# 2025-03-23.net
KiCad netlist of a schematic drawn in EasyEDA
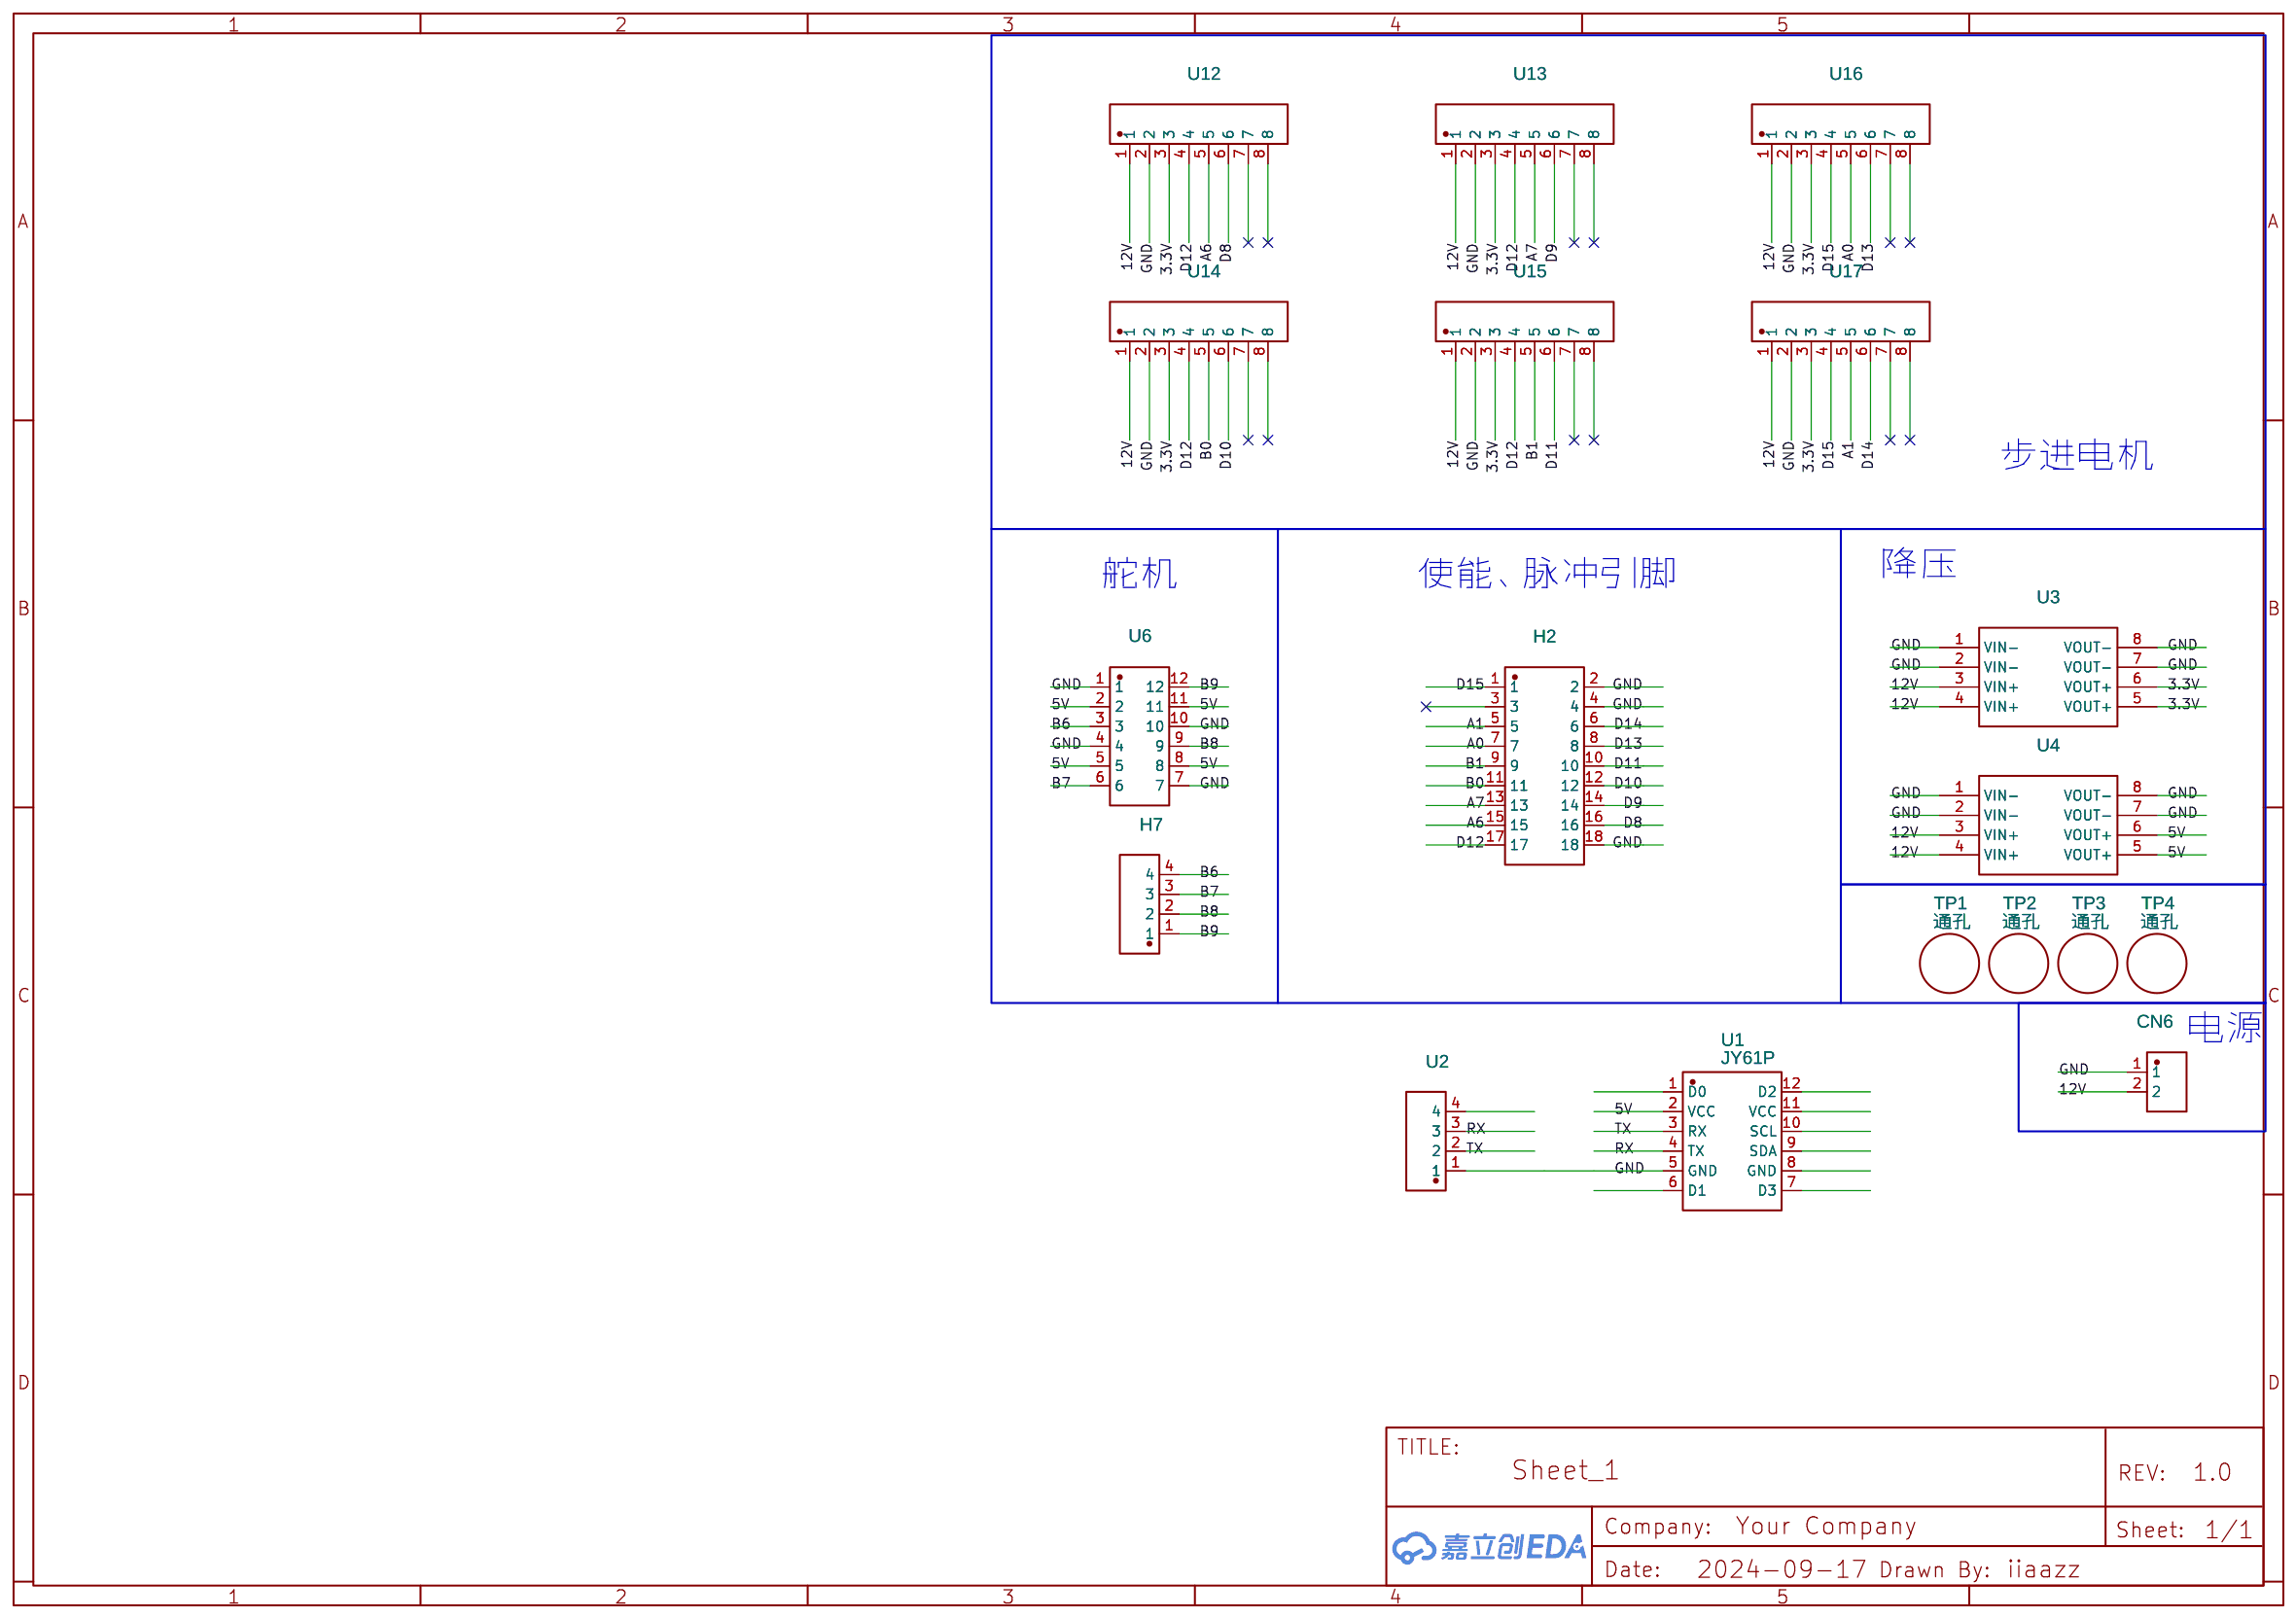
[diagram p0: schematic sheet]

(export (version "E")
  (design (tool "Eeschema 10.0.6"))
  (components
    (comp (ref "CN6")
      (value "DB2ERC-3.81-2P")
      (fields
        (field (name "Manufacturer Part") "DB2ERC-3.81-2P-GN")
        (field (name "Manufacturer") "DORABO(地博电气)")
      )
      (libsource (lib "") (part "DB2ERC-3.81-2P"))
    )
    (comp (ref "H2")
      (value "PZ254-2-09-W-8.5")
      (fields (field (name "Manufacturer") "HCTL(华灿天禄)"))
      (libsource (lib "") (part "PZ254-2-09-W-8.5"))
    )
    (comp (ref "H7")
      (value "PZ254V-11-04P_C2691448")
      (fields (field (name "Manufacturer Part") "PZ254V-11-04P") (field (name "Manufacturer") "XFCN(兴飞)"))
      (libsource (lib "") (part "PZ254V-11-04P_C2691448"))
    )
    (comp (ref "TP1") (value "通孔") (libsource (lib "") (part "通孔")))
    (comp (ref "TP2") (value "通孔") (libsource (lib "") (part "通孔")))
    (comp (ref "TP3") (value "通孔") (libsource (lib "") (part "通孔")))
    (comp (ref "TP4") (value "通孔") (libsource (lib "") (part "通孔")))
    (comp (ref "U1") (value "JY61P") (libsource (lib "") (part "JY61P")))
    (comp (ref "U2")
      (value "XH2.54-4P_C9900011138")
      (fields (field (name "Manufacturer Part") "XH2.54-4P"))
      (libsource (lib "") (part "XH2.54-4P_C9900011138"))
    )
    (comp (ref "U3") (value "MP1584EN") (libsource (lib "") (part "MP1584EN-LF-Z")))
    (comp (ref "U4") (value "MP1584EN") (libsource (lib "") (part "MP1584EN-LF-Z")))
    (comp (ref "U6")
      (value "HX PZ2.54-3X4P ZZ")
      (fields
        (field (name "Manufacturer Part") "HX PZ2.54-3x4P ZZ")
        (field (name "Manufacturer") "hanxia(韩下)")
      )
      (libsource (lib "") (part "HX PZ2.54-3X4P ZZ"))
    )
    (comp (ref "U12")
      (value "ZX-XH2.54-8PWZ")
      (fields (field (name "Manufacturer") "Megastar(兆星)"))
      (libsource (lib "") (part "ZX-XH2.54-8PWZ"))
    )
    (comp (ref "U13")
      (value "ZX-XH2.54-8PWZ")
      (fields (field (name "Manufacturer") "Megastar(兆星)"))
      (libsource (lib "") (part "ZX-XH2.54-8PWZ"))
    )
    (comp (ref "U14")
      (value "ZX-XH2.54-8PWZ")
      (fields (field (name "Manufacturer") "Megastar(兆星)"))
      (libsource (lib "") (part "ZX-XH2.54-8PWZ"))
    )
    (comp (ref "U15")
      (value "ZX-XH2.54-8PWZ")
      (fields (field (name "Manufacturer") "Megastar(兆星)"))
      (libsource (lib "") (part "ZX-XH2.54-8PWZ"))
    )
    (comp (ref "U16")
      (value "ZX-XH2.54-8PWZ")
      (fields (field (name "Manufacturer") "Megastar(兆星)"))
      (libsource (lib "") (part "ZX-XH2.54-8PWZ"))
    )
    (comp (ref "U17")
      (value "ZX-XH2.54-8PWZ")
      (fields (field (name "Manufacturer") "Megastar(兆星)"))
      (libsource (lib "") (part "ZX-XH2.54-8PWZ"))
    )
  )
  (nets
    (net (code "1") (name "/3.3V") (class "Default")
      (node (ref "U12") (pin "3") (pinfunction "3_3") (pintype "unspecified"))
      (node (ref "U13") (pin "3") (pinfunction "3_3") (pintype "unspecified"))
      (node (ref "U14") (pin "3") (pinfunction "3_3") (pintype "unspecified"))
      (node (ref "U15") (pin "3") (pinfunction "3_3") (pintype "unspecified"))
      (node (ref "U16") (pin "3") (pinfunction "3_3") (pintype "unspecified"))
      (node (ref "U17") (pin "3") (pinfunction "3_3") (pintype "unspecified"))
      (node (ref "U3") (pin "5") (pinfunction "VOUT+_5") (pintype "unspecified"))
      (node (ref "U3") (pin "6") (pinfunction "VOUT+_6") (pintype "unspecified"))
    )
    (net (code "2") (name "/5V") (class "Default")
      (node (ref "U1") (pin "2") (pinfunction "VCC_2") (pintype "unspecified"))
      (node (ref "U4") (pin "5") (pinfunction "VOUT+_5") (pintype "unspecified"))
      (node (ref "U4") (pin "6") (pinfunction "VOUT+_6") (pintype "unspecified"))
      (node (ref "U6") (pin "11") (pinfunction "11_11") (pintype "unspecified"))
      (node (ref "U6") (pin "2") (pinfunction "2_2") (pintype "unspecified"))
      (node (ref "U6") (pin "5") (pinfunction "5_5") (pintype "unspecified"))
      (node (ref "U6") (pin "8") (pinfunction "8_8") (pintype "unspecified"))
    )
    (net (code "3") (name "/12V") (class "Default")
      (node (ref "CN6") (pin "2") (pinfunction "2_2") (pintype "unspecified"))
      (node (ref "U12") (pin "1") (pinfunction "1_1") (pintype "unspecified"))
      (node (ref "U13") (pin "1") (pinfunction "1_1") (pintype "unspecified"))
      (node (ref "U14") (pin "1") (pinfunction "1_1") (pintype "unspecified"))
      (node (ref "U15") (pin "1") (pinfunction "1_1") (pintype "unspecified"))
      (node (ref "U16") (pin "1") (pinfunction "1_1") (pintype "unspecified"))
      (node (ref "U17") (pin "1") (pinfunction "1_1") (pintype "unspecified"))
      (node (ref "U3") (pin "3") (pinfunction "VIN+_3") (pintype "unspecified"))
      (node (ref "U3") (pin "4") (pinfunction "VIN+_4") (pintype "unspecified"))
      (node (ref "U4") (pin "3") (pinfunction "VIN+_3") (pintype "unspecified"))
      (node (ref "U4") (pin "4") (pinfunction "VIN+_4") (pintype "unspecified"))
    )
    (net (code "4") (name "/A0") (class "Default")
      (node (ref "H2") (pin "7") (pinfunction "7_7") (pintype "unspecified"))
      (node (ref "U16") (pin "5") (pinfunction "5_5") (pintype "unspecified"))
    )
    (net (code "5") (name "/A1") (class "Default")
      (node (ref "H2") (pin "5") (pinfunction "5_5") (pintype "unspecified"))
      (node (ref "U17") (pin "5") (pinfunction "5_5") (pintype "unspecified"))
    )
    (net (code "6") (name "/A6") (class "Default")
      (node (ref "H2") (pin "15") (pinfunction "15_15") (pintype "unspecified"))
      (node (ref "U12") (pin "5") (pinfunction "5_5") (pintype "unspecified"))
    )
    (net (code "7") (name "/A7") (class "Default")
      (node (ref "H2") (pin "13") (pinfunction "13_13") (pintype "unspecified"))
      (node (ref "U13") (pin "5") (pinfunction "5_5") (pintype "unspecified"))
    )
    (net (code "8") (name "/B0") (class "Default")
      (node (ref "H2") (pin "11") (pinfunction "11_11") (pintype "unspecified"))
      (node (ref "U14") (pin "5") (pinfunction "5_5") (pintype "unspecified"))
    )
    (net (code "9") (name "/B1") (class "Default")
      (node (ref "H2") (pin "9") (pinfunction "9_9") (pintype "unspecified"))
      (node (ref "U15") (pin "5") (pinfunction "5_5") (pintype "unspecified"))
    )
    (net (code "10") (name "/B6") (class "Default")
      (node (ref "H7") (pin "4") (pinfunction "4_4") (pintype "unspecified"))
      (node (ref "U6") (pin "3") (pinfunction "3_3") (pintype "unspecified"))
    )
    (net (code "11") (name "/B7") (class "Default")
      (node (ref "H7") (pin "3") (pinfunction "3_3") (pintype "unspecified"))
      (node (ref "U6") (pin "6") (pinfunction "6_6") (pintype "unspecified"))
    )
    (net (code "12") (name "/B8") (class "Default")
      (node (ref "H7") (pin "2") (pinfunction "2_2") (pintype "unspecified"))
      (node (ref "U6") (pin "9") (pinfunction "9_9") (pintype "unspecified"))
    )
    (net (code "13") (name "/B9") (class "Default")
      (node (ref "H7") (pin "1") (pinfunction "1_1") (pintype "unspecified"))
      (node (ref "U6") (pin "12") (pinfunction "12_12") (pintype "unspecified"))
    )
    (net (code "14") (name "/D8") (class "Default")
      (node (ref "H2") (pin "16") (pinfunction "16_16") (pintype "unspecified"))
      (node (ref "U12") (pin "6") (pinfunction "6_6") (pintype "unspecified"))
    )
    (net (code "15") (name "/D9") (class "Default")
      (node (ref "H2") (pin "14") (pinfunction "14_14") (pintype "unspecified"))
      (node (ref "U13") (pin "6") (pinfunction "6_6") (pintype "unspecified"))
    )
    (net (code "16") (name "/D10") (class "Default")
      (node (ref "H2") (pin "12") (pinfunction "12_12") (pintype "unspecified"))
      (node (ref "U14") (pin "6") (pinfunction "6_6") (pintype "unspecified"))
    )
    (net (code "17") (name "/D11") (class "Default")
      (node (ref "H2") (pin "10") (pinfunction "10_10") (pintype "unspecified"))
      (node (ref "U15") (pin "6") (pinfunction "6_6") (pintype "unspecified"))
    )
    (net (code "18") (name "/D12") (class "Default")
      (node (ref "H2") (pin "17") (pinfunction "17_17") (pintype "unspecified"))
      (node (ref "U12") (pin "4") (pinfunction "4_4") (pintype "unspecified"))
      (node (ref "U13") (pin "4") (pinfunction "4_4") (pintype "unspecified"))
      (node (ref "U14") (pin "4") (pinfunction "4_4") (pintype "unspecified"))
      (node (ref "U15") (pin "4") (pinfunction "4_4") (pintype "unspecified"))
    )
    (net (code "19") (name "/D13") (class "Default")
      (node (ref "H2") (pin "8") (pinfunction "8_8") (pintype "unspecified"))
      (node (ref "U16") (pin "6") (pinfunction "6_6") (pintype "unspecified"))
    )
    (net (code "20") (name "/D14") (class "Default")
      (node (ref "H2") (pin "6") (pinfunction "6_6") (pintype "unspecified"))
      (node (ref "U17") (pin "6") (pinfunction "6_6") (pintype "unspecified"))
    )
    (net (code "21") (name "/D15") (class "Default")
      (node (ref "H2") (pin "1") (pinfunction "1_1") (pintype "unspecified"))
      (node (ref "U16") (pin "4") (pinfunction "4_4") (pintype "unspecified"))
      (node (ref "U17") (pin "4") (pinfunction "4_4") (pintype "unspecified"))
    )
    (net (code "22") (name "/GND") (class "Default")
      (node (ref "CN6") (pin "1") (pinfunction "1_1") (pintype "unspecified"))
      (node (ref "H2") (pin "18") (pinfunction "18_18") (pintype "unspecified"))
      (node (ref "H2") (pin "2") (pinfunction "2_2") (pintype "unspecified"))
      (node (ref "H2") (pin "4") (pinfunction "4_4") (pintype "unspecified"))
      (node (ref "U1") (pin "5") (pinfunction "GND_5") (pintype "unspecified"))
      (node (ref "U12") (pin "2") (pinfunction "2_2") (pintype "unspecified"))
      (node (ref "U13") (pin "2") (pinfunction "2_2") (pintype "unspecified"))
      (node (ref "U14") (pin "2") (pinfunction "2_2") (pintype "unspecified"))
      (node (ref "U15") (pin "2") (pinfunction "2_2") (pintype "unspecified"))
      (node (ref "U16") (pin "2") (pinfunction "2_2") (pintype "unspecified"))
      (node (ref "U17") (pin "2") (pinfunction "2_2") (pintype "unspecified"))
      (node (ref "U2") (pin "1") (pinfunction "1_1") (pintype "unspecified"))
      (node (ref "U3") (pin "1") (pinfunction "VIN-_1") (pintype "unspecified"))
      (node (ref "U3") (pin "2") (pinfunction "VIN-_2") (pintype "unspecified"))
      (node (ref "U3") (pin "7") (pinfunction "VOUT-_7") (pintype "unspecified"))
      (node (ref "U3") (pin "8") (pinfunction "VOUT-_8") (pintype "unspecified"))
      (node (ref "U4") (pin "1") (pinfunction "VIN-_1") (pintype "unspecified"))
      (node (ref "U4") (pin "2") (pinfunction "VIN-_2") (pintype "unspecified"))
      (node (ref "U4") (pin "7") (pinfunction "VOUT-_7") (pintype "unspecified"))
      (node (ref "U4") (pin "8") (pinfunction "VOUT-_8") (pintype "unspecified"))
      (node (ref "U6") (pin "1") (pinfunction "1_1") (pintype "unspecified"))
      (node (ref "U6") (pin "10") (pinfunction "10_10") (pintype "unspecified"))
      (node (ref "U6") (pin "4") (pinfunction "4_4") (pintype "unspecified"))
      (node (ref "U6") (pin "7") (pinfunction "7_7") (pintype "unspecified"))
    )
    (net (code "23") (name "/RX") (class "Default")
      (node (ref "U1") (pin "4") (pinfunction "TX_4") (pintype "unspecified"))
      (node (ref "U2") (pin "3") (pinfunction "3_3") (pintype "unspecified"))
    )
    (net (code "24") (name "/TX") (class "Default")
      (node (ref "U1") (pin "3") (pinfunction "RX_3") (pintype "unspecified"))
      (node (ref "U2") (pin "2") (pinfunction "2_2") (pintype "unspecified"))
    )
    (net (code "25") (name "unconnected-(H2-Pad3)") (class "Default")
      (node (ref "H2") (pin "3") (pinfunction "3_3") (pintype "unspecified+no_connect"))
    )
    (net (code "26") (name "unconnected-(U1-D0-Pad1)") (class "Default")
      (node (ref "U1") (pin "1") (pinfunction "D0_1") (pintype "unspecified"))
    )
    (net (code "27") (name "unconnected-(U1-D1-Pad6)") (class "Default")
      (node (ref "U1") (pin "6") (pinfunction "D1_6") (pintype "unspecified"))
    )
    (net (code "28") (name "unconnected-(U1-D2-Pad12)") (class "Default")
      (node (ref "U1") (pin "12") (pinfunction "D2_12") (pintype "unspecified"))
    )
    (net (code "29") (name "unconnected-(U1-D3-Pad7)") (class "Default")
      (node (ref "U1") (pin "7") (pinfunction "D3_7") (pintype "unspecified"))
    )
    (net (code "30") (name "unconnected-(U1-GND-Pad8)") (class "Default")
      (node (ref "U1") (pin "8") (pinfunction "GND_8") (pintype "unspecified"))
    )
    (net (code "31") (name "unconnected-(U1-SCL-Pad10)") (class "Default")
      (node (ref "U1") (pin "10") (pinfunction "SCL_10") (pintype "unspecified"))
    )
    (net (code "32") (name "unconnected-(U1-SDA-Pad9)") (class "Default")
      (node (ref "U1") (pin "9") (pinfunction "SDA_9") (pintype "unspecified"))
    )
    (net (code "33") (name "unconnected-(U1-VCC-Pad11)") (class "Default")
      (node (ref "U1") (pin "11") (pinfunction "VCC_11") (pintype "unspecified"))
    )
    (net (code "34") (name "unconnected-(U2-Pad4)") (class "Default")
      (node (ref "U2") (pin "4") (pinfunction "4_4") (pintype "unspecified"))
    )
    (net (code "35") (name "unconnected-(U12-Pad7)") (class "Default")
      (node (ref "U12") (pin "7") (pinfunction "7_7") (pintype "unspecified+no_connect"))
    )
    (net (code "36") (name "unconnected-(U12-Pad8)") (class "Default")
      (node (ref "U12") (pin "8") (pinfunction "8_8") (pintype "unspecified+no_connect"))
    )
    (net (code "37") (name "unconnected-(U13-Pad7)") (class "Default")
      (node (ref "U13") (pin "7") (pinfunction "7_7") (pintype "unspecified+no_connect"))
    )
    (net (code "38") (name "unconnected-(U13-Pad8)") (class "Default")
      (node (ref "U13") (pin "8") (pinfunction "8_8") (pintype "unspecified+no_connect"))
    )
    (net (code "39") (name "unconnected-(U14-Pad7)") (class "Default")
      (node (ref "U14") (pin "7") (pinfunction "7_7") (pintype "unspecified+no_connect"))
    )
    (net (code "40") (name "unconnected-(U14-Pad8)") (class "Default")
      (node (ref "U14") (pin "8") (pinfunction "8_8") (pintype "unspecified+no_connect"))
    )
    (net (code "41") (name "unconnected-(U15-Pad7)") (class "Default")
      (node (ref "U15") (pin "7") (pinfunction "7_7") (pintype "unspecified+no_connect"))
    )
    (net (code "42") (name "unconnected-(U15-Pad8)") (class "Default")
      (node (ref "U15") (pin "8") (pinfunction "8_8") (pintype "unspecified+no_connect"))
    )
    (net (code "43") (name "unconnected-(U16-Pad7)") (class "Default")
      (node (ref "U16") (pin "7") (pinfunction "7_7") (pintype "unspecified+no_connect"))
    )
    (net (code "44") (name "unconnected-(U16-Pad8)") (class "Default")
      (node (ref "U16") (pin "8") (pinfunction "8_8") (pintype "unspecified+no_connect"))
    )
    (net (code "45") (name "unconnected-(U17-Pad7)") (class "Default")
      (node (ref "U17") (pin "7") (pinfunction "7_7") (pintype "unspecified+no_connect"))
    )
    (net (code "46") (name "unconnected-(U17-Pad8)") (class "Default")
      (node (ref "U17") (pin "8") (pinfunction "8_8") (pintype "unspecified+no_connect"))
    )
  )
)
